# demoBoard.net
KiCad netlist of a schematic drawn in Altium Designer
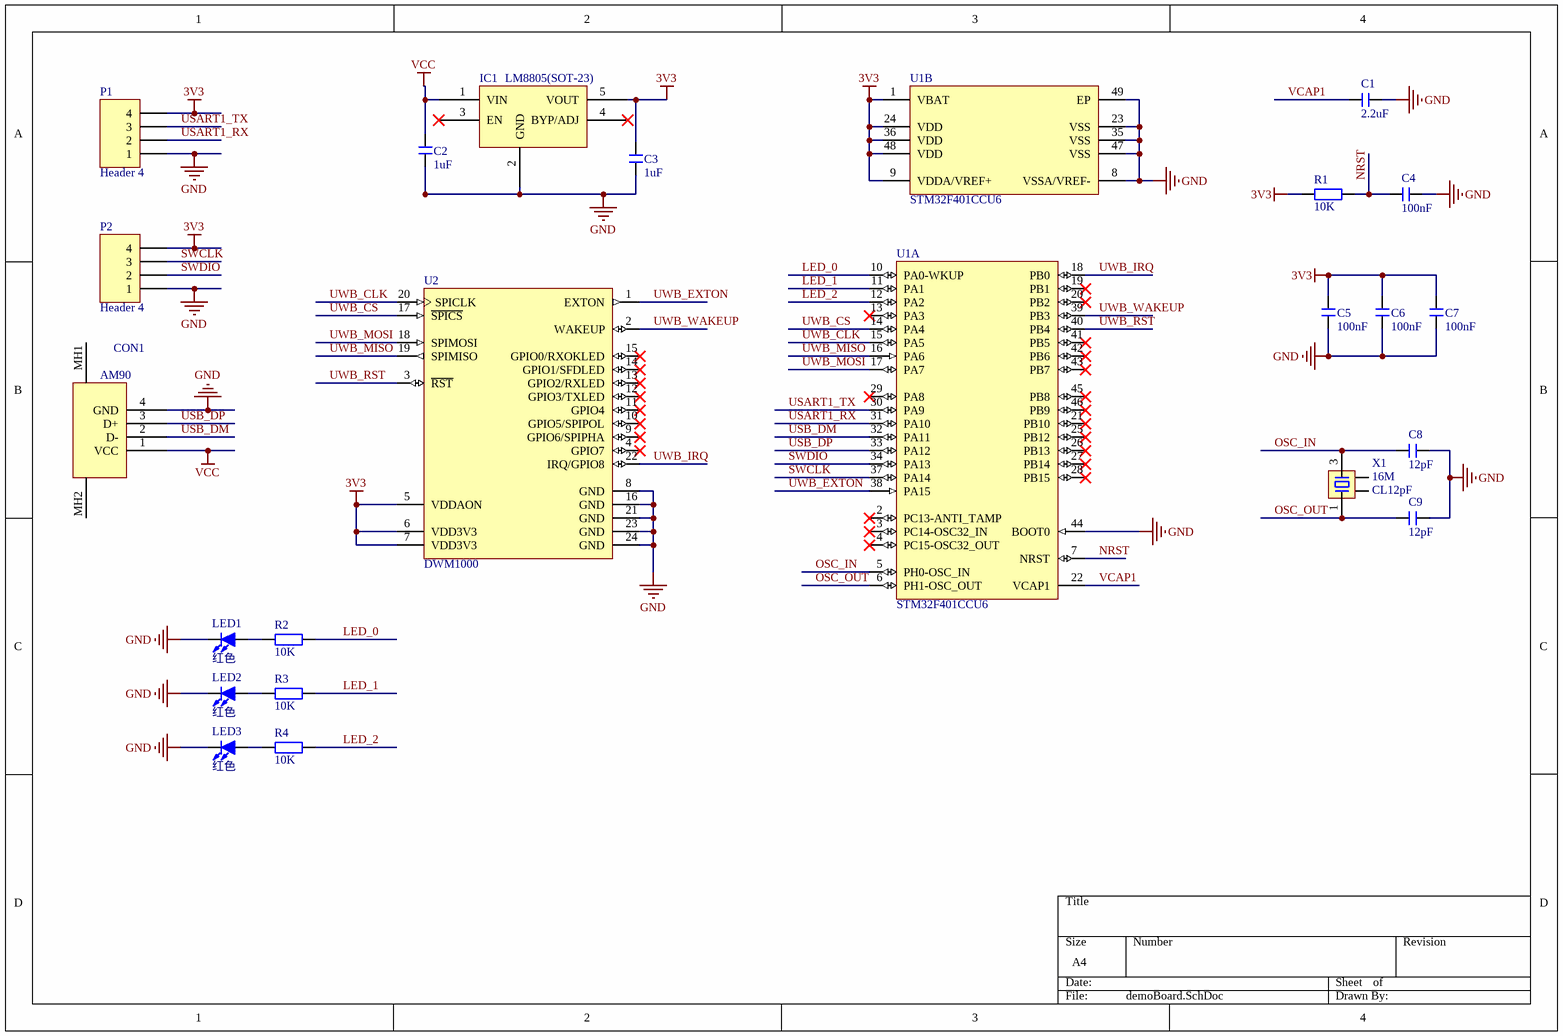
[diagram p0: demoBoard.SchDoc]

(export (version "E")
  (design (tool "Eeschema 10.0.6"))
  (components
    (comp (ref "C1")
      (value "2.2uF")
      (footprint "C 0603_L")
      (description "无极性贴片电容")
      (fields (field (name "版权归属") "源创客"))
      (libsource (lib "3.1   - 电阻-电容-电感") (part "C"))
    )
    (comp (ref "C2")
      (value "1uF")
      (footprint "C 0603_L")
      (description "无极性贴片电容")
      (fields (field (name "版权归属") "源创客"))
      (libsource (lib "3.1   - 电阻-电容-电感") (part "C"))
    )
    (comp (ref "C3")
      (value "1uF")
      (footprint "C 0603_L")
      (description "无极性贴片电容")
      (fields (field (name "版权归属") "源创客"))
      (libsource (lib "3.1   - 电阻-电容-电感") (part "C"))
    )
    (comp (ref "C4")
      (value "100nF")
      (footprint "C 0603_L")
      (description "无极性贴片电容")
      (fields (field (name "版权归属") "源创客"))
      (libsource (lib "3.1   - 电阻-电容-电感") (part "C"))
    )
    (comp (ref "C5")
      (value "100nF")
      (footprint "C 0603_L")
      (description "无极性贴片电容")
      (fields (field (name "版权归属") "源创客"))
      (libsource (lib "3.1   - 电阻-电容-电感") (part "C"))
    )
    (comp (ref "C6")
      (value "100nF")
      (footprint "C 0603_L")
      (description "无极性贴片电容")
      (fields (field (name "版权归属") "源创客"))
      (libsource (lib "3.1   - 电阻-电容-电感") (part "C"))
    )
    (comp (ref "C7")
      (value "100nF")
      (footprint "C 0603_L")
      (description "无极性贴片电容")
      (fields (field (name "版权归属") "源创客"))
      (libsource (lib "3.1   - 电阻-电容-电感") (part "C"))
    )
    (comp (ref "C8")
      (value "12pF")
      (footprint "C 0603_L")
      (description "无极性贴片电容")
      (fields (field (name "版权归属") "源创客"))
      (libsource (lib "3.1   - 电阻-电容-电感") (part "C"))
    )
    (comp (ref "C9")
      (value "12pF")
      (footprint "C 0603_L")
      (description "无极性贴片电容")
      (fields (field (name "版权归属") "源创客"))
      (libsource (lib "3.1   - 电阻-电容-电感") (part "C"))
    )
    (comp (ref "CON1") (value "AM90") (footprint "USB-AM-TH_AM90") (libsource (lib "Schlib") (part "AM90")))
    (comp (ref "IC1")
      (value "LM8805(SOT-23)")
      (footprint "SOT23-5N")
      (description "600mA CMOS L.D.O. Regulator")
      (libsource (lib "1.3   - 电源类芯片") (part "LM8805(SOT-23)"))
    )
    (comp (ref "LED1")
      (value "红色")
      (footprint "LED 0603G")
      (description "贴片LED")
      (fields (field (name "版权归属") "源创客"))
      (libsource (lib "9.1   - LED") (part "LED-SMD"))
    )
    (comp (ref "LED2")
      (value "红色")
      (footprint "LED 0603G")
      (description "贴片LED")
      (fields (field (name "版权归属") "源创客"))
      (libsource (lib "9.1   - LED") (part "LED-SMD"))
    )
    (comp (ref "LED3")
      (value "红色")
      (footprint "LED 0603G")
      (description "贴片LED")
      (fields (field (name "版权归属") "源创客"))
      (libsource (lib "9.1   - LED") (part "LED-SMD"))
    )
    (comp (ref "P1")
      (value "Header 4")
      (footprint "MX 1.25-WS-4P")
      (description "Header, 4-Pin")
      (fields (field (name "PUBLISHER") "Altium Limited"))
      (libsource (lib "Miscellaneous Connectors") (part "Header 4"))
    )
    (comp (ref "P2")
      (value "Header 4")
      (footprint "MX 1.25-WS-4P")
      (description "Header, 4-Pin")
      (fields (field (name "PUBLISHER") "Altium Limited"))
      (libsource (lib "Miscellaneous Connectors") (part "Header 4"))
    )
    (comp (ref "R1")
      (value "10K")
      (footprint "R 0603_L")
      (description "贴片电阻")
      (fields (field (name "版权归属") "源创客"))
      (libsource (lib "3.1   - 电阻-电容-电感") (part "R"))
    )
    (comp (ref "R2")
      (value "10K")
      (footprint "R 0603_L")
      (description "贴片电阻")
      (fields (field (name "版权归属") "源创客"))
      (libsource (lib "3.1   - 电阻-电容-电感") (part "R"))
    )
    (comp (ref "R3")
      (value "10K")
      (footprint "R 0603_L")
      (description "贴片电阻")
      (fields (field (name "版权归属") "源创客"))
      (libsource (lib "3.1   - 电阻-电容-电感") (part "R"))
    )
    (comp (ref "R4")
      (value "10K")
      (footprint "R 0603_L")
      (description "贴片电阻")
      (fields (field (name "版权归属") "源创客"))
      (libsource (lib "3.1   - 电阻-电容-电感") (part "R"))
    )
    (comp (ref "U1")
      (value "STM32F401CCU6")
      (footprint "STM-UFQFPN48_N")
      (fields (field (name "MANUFACTURER") "STMicroelectronics"))
      (libsource (lib "Altium Content Vault") (part "MC-ARM-STM32F401-SQ48"))
    )
    (comp (ref "U2")
      (value "DWM1000")
      (footprint "DECW-DWM1000-24_V")
      (description "DW M1000 IEEE 802.15.4 -2011 UWB Transceiver Module")
      (fields (field (name "MANUFACTURER") "Decawave"))
      (libsource (lib "Altium Content Vault") (part "DECW-DWM1000-24"))
    )
    (comp (ref "X1")
      (value "16M")
      (footprint "OSC 3225-4P")
      (description "4脚无源晶振")
      (fields (field (name "负载电容") "CL12pF") (field (name "版权归属") "源创客"))
      (libsource (lib "10.1 - 保险丝-晶振") (part "XTAL-4P"))
    )
  )
  (nets
    (net (code "1") (name "/LED_0") (class "Default")
      (node (ref "R2") (pin "2") (pinfunction "2_2") (pintype "passive"))
      (node (ref "U1") (pin "10") (pinfunction "PA0-WKUP_10") (pintype "bidirectional"))
    )
    (net (code "2") (name "/LED_1") (class "Default")
      (node (ref "R3") (pin "2") (pinfunction "2_2") (pintype "passive"))
      (node (ref "U1") (pin "11") (pinfunction "PA1_11") (pintype "bidirectional"))
    )
    (net (code "3") (name "/LED_2") (class "Default")
      (node (ref "R4") (pin "2") (pinfunction "2_2") (pintype "passive"))
      (node (ref "U1") (pin "12") (pinfunction "PA2_12") (pintype "bidirectional"))
    )
    (net (code "4") (name "/NRST") (class "Default")
      (node (ref "C4") (pin "2") (pinfunction "2_2") (pintype "passive"))
      (node (ref "R1") (pin "2") (pinfunction "2_2") (pintype "passive"))
      (node (ref "U1") (pin "7") (pinfunction "NRST_7") (pintype "bidirectional"))
    )
    (net (code "5") (name "/OSC_IN") (class "Default")
      (node (ref "C8") (pin "1") (pinfunction "1_1") (pintype "passive"))
      (node (ref "U1") (pin "5") (pinfunction "PH0-OSC_IN_5") (pintype "bidirectional"))
      (node (ref "X1") (pin "3") (pinfunction "3_3") (pintype "passive"))
    )
    (net (code "6") (name "/OSC_OUT") (class "Default")
      (node (ref "C9") (pin "1") (pinfunction "1_1") (pintype "passive"))
      (node (ref "U1") (pin "6") (pinfunction "PH1-OSC_OUT_6") (pintype "bidirectional"))
      (node (ref "X1") (pin "1") (pinfunction "1_1") (pintype "passive"))
    )
    (net (code "7") (name "/SWCLK") (class "Default")
      (node (ref "P2") (pin "3") (pinfunction "3_3") (pintype "passive"))
      (node (ref "U1") (pin "37") (pinfunction "PA14_37") (pintype "bidirectional"))
    )
    (net (code "8") (name "/SWDIO") (class "Default")
      (node (ref "P2") (pin "2") (pinfunction "2_2") (pintype "passive"))
      (node (ref "U1") (pin "34") (pinfunction "PA13_34") (pintype "bidirectional"))
    )
    (net (code "9") (name "/USART1_RX") (class "Default")
      (node (ref "P1") (pin "2") (pinfunction "2_2") (pintype "passive"))
      (node (ref "U1") (pin "31") (pinfunction "PA10_31") (pintype "bidirectional"))
    )
    (net (code "10") (name "/USART1_TX") (class "Default")
      (node (ref "P1") (pin "3") (pinfunction "3_3") (pintype "passive"))
      (node (ref "U1") (pin "30") (pinfunction "PA9_30") (pintype "bidirectional"))
    )
    (net (code "11") (name "/USB_DM") (class "Default")
      (node (ref "CON1") (pin "2") (pinfunction "D-_2") (pintype "passive"))
      (node (ref "U1") (pin "32") (pinfunction "PA11_32") (pintype "bidirectional"))
    )
    (net (code "12") (name "/USB_DP") (class "Default")
      (node (ref "CON1") (pin "3") (pinfunction "D+_3") (pintype "passive"))
      (node (ref "U1") (pin "33") (pinfunction "PA12_33") (pintype "bidirectional"))
    )
    (net (code "13") (name "/UWB_CLK") (class "Default")
      (node (ref "U1") (pin "15") (pinfunction "PA5_15") (pintype "bidirectional"))
      (node (ref "U2") (pin "20") (pinfunction "SPICLK_20") (pintype "input"))
    )
    (net (code "14") (name "/UWB_CS") (class "Default")
      (node (ref "U1") (pin "14") (pinfunction "PA4_14") (pintype "bidirectional"))
      (node (ref "U2") (pin "17") (pinfunction "~{SPICS}_17") (pintype "input"))
    )
    (net (code "15") (name "/UWB_EXTON") (class "Default")
      (node (ref "U1") (pin "38") (pinfunction "PA15_38") (pintype "input"))
      (node (ref "U2") (pin "1") (pinfunction "EXTON_1") (pintype "output"))
    )
    (net (code "16") (name "/UWB_IRQ") (class "Default")
      (node (ref "U1") (pin "18") (pinfunction "PB0_18") (pintype "bidirectional"))
      (node (ref "U2") (pin "22") (pinfunction "IRQ/GPIO8_22") (pintype "bidirectional"))
    )
    (net (code "17") (name "/UWB_MISO") (class "Default")
      (node (ref "U1") (pin "16") (pinfunction "PA6_16") (pintype "input"))
      (node (ref "U2") (pin "19") (pinfunction "SPIMISO_19") (pintype "output"))
    )
    (net (code "18") (name "/UWB_MOSI") (class "Default")
      (node (ref "U1") (pin "17") (pinfunction "PA7_17") (pintype "bidirectional"))
      (node (ref "U2") (pin "18") (pinfunction "SPIMOSI_18") (pintype "input"))
    )
    (net (code "19") (name "/UWB_RST") (class "Default")
      (node (ref "U1") (pin "40") (pinfunction "PB4_40") (pintype "bidirectional"))
      (node (ref "U2") (pin "3") (pinfunction "~{RST}_3") (pintype "bidirectional"))
    )
    (net (code "20") (name "/UWB_WAKEUP") (class "Default")
      (node (ref "U1") (pin "39") (pinfunction "PB3_39") (pintype "bidirectional"))
      (node (ref "U2") (pin "2") (pinfunction "WAKEUP_2") (pintype "bidirectional"))
    )
    (net (code "21") (name "/VCAP1") (class "Default")
      (node (ref "C1") (pin "1") (pinfunction "1_1") (pintype "passive"))
      (node (ref "U1") (pin "22") (pinfunction "VCAP1_22") (pintype "power_in"))
    )
    (net (code "22") (name "3V3") (class "Default")
      (node (ref "C3") (pin "2") (pinfunction "2_2") (pintype "passive"))
      (node (ref "C5") (pin "2") (pinfunction "2_2") (pintype "passive"))
      (node (ref "C6") (pin "2") (pinfunction "2_2") (pintype "passive"))
      (node (ref "C7") (pin "2") (pinfunction "2_2") (pintype "passive"))
      (node (ref "IC1") (pin "5") (pinfunction "VOUT_5") (pintype "passive"))
      (node (ref "P1") (pin "4") (pinfunction "4_4") (pintype "passive"))
      (node (ref "P2") (pin "4") (pinfunction "4_4") (pintype "passive"))
      (node (ref "R1") (pin "1") (pinfunction "1_1") (pintype "passive"))
      (node (ref "U1") (pin "1") (pinfunction "VBAT_1") (pintype "power_in"))
      (node (ref "U1") (pin "24") (pinfunction "VDD_24") (pintype "power_in"))
      (node (ref "U1") (pin "36") (pinfunction "VDD_36") (pintype "power_in"))
      (node (ref "U1") (pin "48") (pinfunction "VDD_48") (pintype "power_in"))
      (node (ref "U1") (pin "9") (pinfunction "VDDA/VREF+_9") (pintype "power_in"))
      (node (ref "U2") (pin "5") (pinfunction "VDDAON_5") (pintype "power_in"))
      (node (ref "U2") (pin "6") (pinfunction "VDD3V3_6") (pintype "power_in"))
      (node (ref "U2") (pin "7") (pinfunction "VDD3V3_7") (pintype "power_in"))
    )
    (net (code "23") (name "GND") (class "Default")
      (node (ref "C1") (pin "2") (pinfunction "2_2") (pintype "passive"))
      (node (ref "C2") (pin "1") (pinfunction "1_1") (pintype "passive"))
      (node (ref "C3") (pin "1") (pinfunction "1_1") (pintype "passive"))
      (node (ref "C4") (pin "1") (pinfunction "1_1") (pintype "passive"))
      (node (ref "C5") (pin "1") (pinfunction "1_1") (pintype "passive"))
      (node (ref "C6") (pin "1") (pinfunction "1_1") (pintype "passive"))
      (node (ref "C7") (pin "1") (pinfunction "1_1") (pintype "passive"))
      (node (ref "C8") (pin "2") (pinfunction "2_2") (pintype "passive"))
      (node (ref "C9") (pin "2") (pinfunction "2_2") (pintype "passive"))
      (node (ref "CON1") (pin "4") (pinfunction "GND_4") (pintype "passive"))
      (node (ref "IC1") (pin "2") (pinfunction "GND_2") (pintype "passive"))
      (node (ref "LED1") (pin "2") (pinfunction "K_2") (pintype "passive"))
      (node (ref "LED2") (pin "2") (pinfunction "K_2") (pintype "passive"))
      (node (ref "LED3") (pin "2") (pinfunction "K_2") (pintype "passive"))
      (node (ref "P1") (pin "1") (pinfunction "1_1") (pintype "passive"))
      (node (ref "P2") (pin "1") (pinfunction "1_1") (pintype "passive"))
      (node (ref "U1") (pin "23") (pinfunction "VSS_23") (pintype "power_in"))
      (node (ref "U1") (pin "35") (pinfunction "VSS_35") (pintype "power_in"))
      (node (ref "U1") (pin "44") (pinfunction "BOOT0_44") (pintype "input"))
      (node (ref "U1") (pin "47") (pinfunction "VSS_47") (pintype "power_in"))
      (node (ref "U1") (pin "49") (pinfunction "EP_49") (pintype "power_in"))
      (node (ref "U1") (pin "8") (pinfunction "VSSA/VREF-_8") (pintype "power_in"))
      (node (ref "U2") (pin "16") (pinfunction "GND_16") (pintype "power_in"))
      (node (ref "U2") (pin "21") (pinfunction "GND_21") (pintype "power_in"))
      (node (ref "U2") (pin "23") (pinfunction "GND_23") (pintype "power_in"))
      (node (ref "U2") (pin "24") (pinfunction "GND_24") (pintype "power_in"))
      (node (ref "U2") (pin "8") (pinfunction "GND_8") (pintype "power_in"))
    )
    (net (code "24") (name "Net-(LED1-A)") (class "Default")
      (node (ref "LED1") (pin "1") (pinfunction "A_1") (pintype "passive"))
      (node (ref "R2") (pin "1") (pinfunction "1_1") (pintype "passive"))
    )
    (net (code "25") (name "Net-(LED2-A)") (class "Default")
      (node (ref "LED2") (pin "1") (pinfunction "A_1") (pintype "passive"))
      (node (ref "R3") (pin "1") (pinfunction "1_1") (pintype "passive"))
    )
    (net (code "26") (name "Net-(LED3-A)") (class "Default")
      (node (ref "LED3") (pin "1") (pinfunction "A_1") (pintype "passive"))
      (node (ref "R4") (pin "1") (pinfunction "1_1") (pintype "passive"))
    )
    (net (code "27") (name "VCC") (class "Default")
      (node (ref "C2") (pin "2") (pinfunction "2_2") (pintype "passive"))
      (node (ref "CON1") (pin "1") (pinfunction "VCC_1") (pintype "passive"))
      (node (ref "IC1") (pin "1") (pinfunction "VIN_1") (pintype "passive"))
    )
    (net (code "28") (name "unconnected-(CON1-PadMH1)") (class "Default")
      (node (ref "CON1") (pin "MH1") (pintype "passive"))
    )
    (net (code "29") (name "unconnected-(CON1-PadMH2)") (class "Default")
      (node (ref "CON1") (pin "MH2") (pintype "passive"))
    )
    (net (code "30") (name "unconnected-(IC1-BYP{slash}ADJ-Pad4)") (class "Default")
      (node (ref "IC1") (pin "4") (pinfunction "BYP/ADJ_4") (pintype "passive+no_connect"))
    )
    (net (code "31") (name "unconnected-(IC1-EN-Pad3)") (class "Default")
      (node (ref "IC1") (pin "3") (pinfunction "EN_3") (pintype "passive+no_connect"))
    )
    (net (code "32") (name "unconnected-(U1A-PA3-Pad13)") (class "Default")
      (node (ref "U1") (pin "13") (pinfunction "PA3_13") (pintype "bidirectional+no_connect"))
    )
    (net (code "33") (name "unconnected-(U1A-PA8-Pad29)") (class "Default")
      (node (ref "U1") (pin "29") (pinfunction "PA8_29") (pintype "bidirectional+no_connect"))
    )
    (net (code "34") (name "unconnected-(U1A-PB1-Pad19)") (class "Default")
      (node (ref "U1") (pin "19") (pinfunction "PB1_19") (pintype "bidirectional+no_connect"))
    )
    (net (code "35") (name "unconnected-(U1A-PB2-Pad20)") (class "Default")
      (node (ref "U1") (pin "20") (pinfunction "PB2_20") (pintype "bidirectional+no_connect"))
    )
    (net (code "36") (name "unconnected-(U1A-PB5-Pad41)") (class "Default")
      (node (ref "U1") (pin "41") (pinfunction "PB5_41") (pintype "bidirectional+no_connect"))
    )
    (net (code "37") (name "unconnected-(U1A-PB6-Pad42)") (class "Default")
      (node (ref "U1") (pin "42") (pinfunction "PB6_42") (pintype "bidirectional+no_connect"))
    )
    (net (code "38") (name "unconnected-(U1A-PB7-Pad43)") (class "Default")
      (node (ref "U1") (pin "43") (pinfunction "PB7_43") (pintype "bidirectional+no_connect"))
    )
    (net (code "39") (name "unconnected-(U1A-PB8-Pad45)") (class "Default")
      (node (ref "U1") (pin "45") (pinfunction "PB8_45") (pintype "bidirectional+no_connect"))
    )
    (net (code "40") (name "unconnected-(U1A-PB9-Pad46)") (class "Default")
      (node (ref "U1") (pin "46") (pinfunction "PB9_46") (pintype "bidirectional+no_connect"))
    )
    (net (code "41") (name "unconnected-(U1A-PB10-Pad21)") (class "Default")
      (node (ref "U1") (pin "21") (pinfunction "PB10_21") (pintype "bidirectional+no_connect"))
    )
    (net (code "42") (name "unconnected-(U1A-PB12-Pad25)") (class "Default")
      (node (ref "U1") (pin "25") (pinfunction "PB12_25") (pintype "bidirectional+no_connect"))
    )
    (net (code "43") (name "unconnected-(U1A-PB13-Pad26)") (class "Default")
      (node (ref "U1") (pin "26") (pinfunction "PB13_26") (pintype "bidirectional+no_connect"))
    )
    (net (code "44") (name "unconnected-(U1A-PB14-Pad27)") (class "Default")
      (node (ref "U1") (pin "27") (pinfunction "PB14_27") (pintype "bidirectional+no_connect"))
    )
    (net (code "45") (name "unconnected-(U1A-PB15-Pad28)") (class "Default")
      (node (ref "U1") (pin "28") (pinfunction "PB15_28") (pintype "bidirectional+no_connect"))
    )
    (net (code "46") (name "unconnected-(U1A-PC13-ANTI_TAMP-Pad2)") (class "Default")
      (node (ref "U1") (pin "2") (pinfunction "PC13-ANTI_TAMP_2") (pintype "bidirectional+no_connect"))
    )
    (net (code "47") (name "unconnected-(U1A-PC14-OSC32_IN-Pad3)") (class "Default")
      (node (ref "U1") (pin "3") (pinfunction "PC14-OSC32_IN_3") (pintype "bidirectional+no_connect"))
    )
    (net (code "48") (name "unconnected-(U1A-PC15-OSC32_OUT-Pad4)") (class "Default")
      (node (ref "U1") (pin "4") (pinfunction "PC15-OSC32_OUT_4") (pintype "bidirectional+no_connect"))
    )
    (net (code "49") (name "unconnected-(U2-GPIO0{slash}RXOKLED-Pad15)") (class "Default")
      (node (ref "U2") (pin "15") (pinfunction "GPIO0/RXOKLED_15") (pintype "bidirectional+no_connect"))
    )
    (net (code "50") (name "unconnected-(U2-GPIO1{slash}SFDLED-Pad14)") (class "Default")
      (node (ref "U2") (pin "14") (pinfunction "GPIO1/SFDLED_14") (pintype "bidirectional+no_connect"))
    )
    (net (code "51") (name "unconnected-(U2-GPIO2{slash}RXLED-Pad13)") (class "Default")
      (node (ref "U2") (pin "13") (pinfunction "GPIO2/RXLED_13") (pintype "bidirectional+no_connect"))
    )
    (net (code "52") (name "unconnected-(U2-GPIO3{slash}TXLED-Pad12)") (class "Default")
      (node (ref "U2") (pin "12") (pinfunction "GPIO3/TXLED_12") (pintype "bidirectional+no_connect"))
    )
    (net (code "53") (name "unconnected-(U2-GPIO4-Pad11)") (class "Default")
      (node (ref "U2") (pin "11") (pinfunction "GPIO4_11") (pintype "bidirectional+no_connect"))
    )
    (net (code "54") (name "unconnected-(U2-GPIO5{slash}SPIPOL-Pad10)") (class "Default")
      (node (ref "U2") (pin "10") (pinfunction "GPIO5/SPIPOL_10") (pintype "bidirectional+no_connect"))
    )
    (net (code "55") (name "unconnected-(U2-GPIO6{slash}SPIPHA-Pad9)") (class "Default")
      (node (ref "U2") (pin "9") (pinfunction "GPIO6/SPIPHA_9") (pintype "bidirectional+no_connect"))
    )
    (net (code "56") (name "unconnected-(U2-GPIO7-Pad4)") (class "Default")
      (node (ref "U2") (pin "4") (pinfunction "GPIO7_4") (pintype "bidirectional+no_connect"))
    )
    (net (code "57") (name "unconnected-(X1-Pad2)") (class "Default")
      (node (ref "X1") (pin "2") (pinfunction "2_2") (pintype "passive"))
    )
    (net (code "58") (name "unconnected-(X1-Pad4)") (class "Default")
      (node (ref "X1") (pin "4") (pinfunction "4_4") (pintype "passive"))
    )
  )
)
